# ticktock.net
KiCad netlist of a schematic drawn in EAGLE
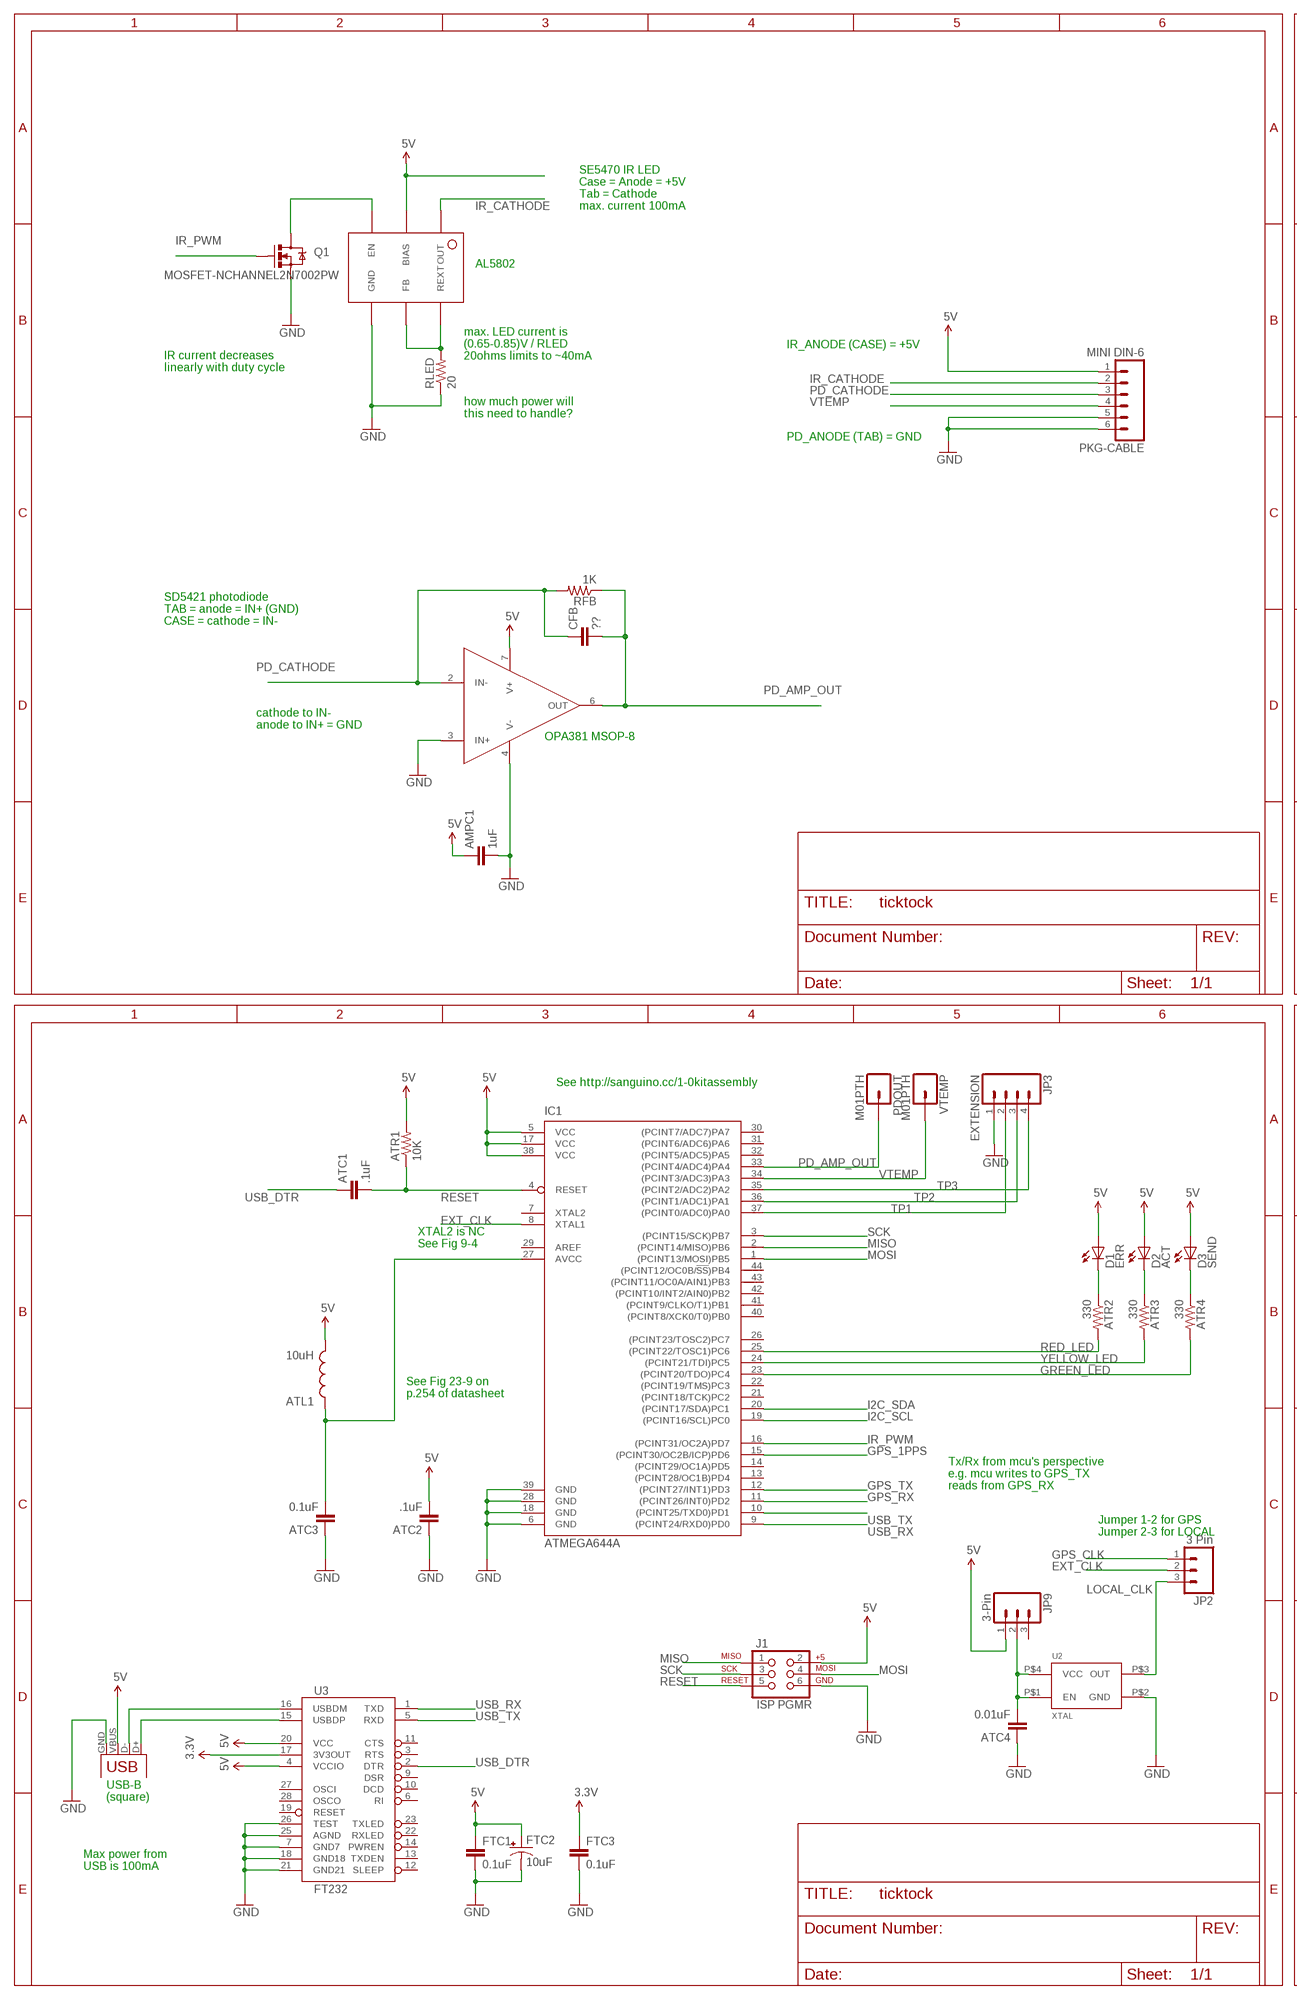
[diagram p0: schematic, sheet 1, part 1 of 2]
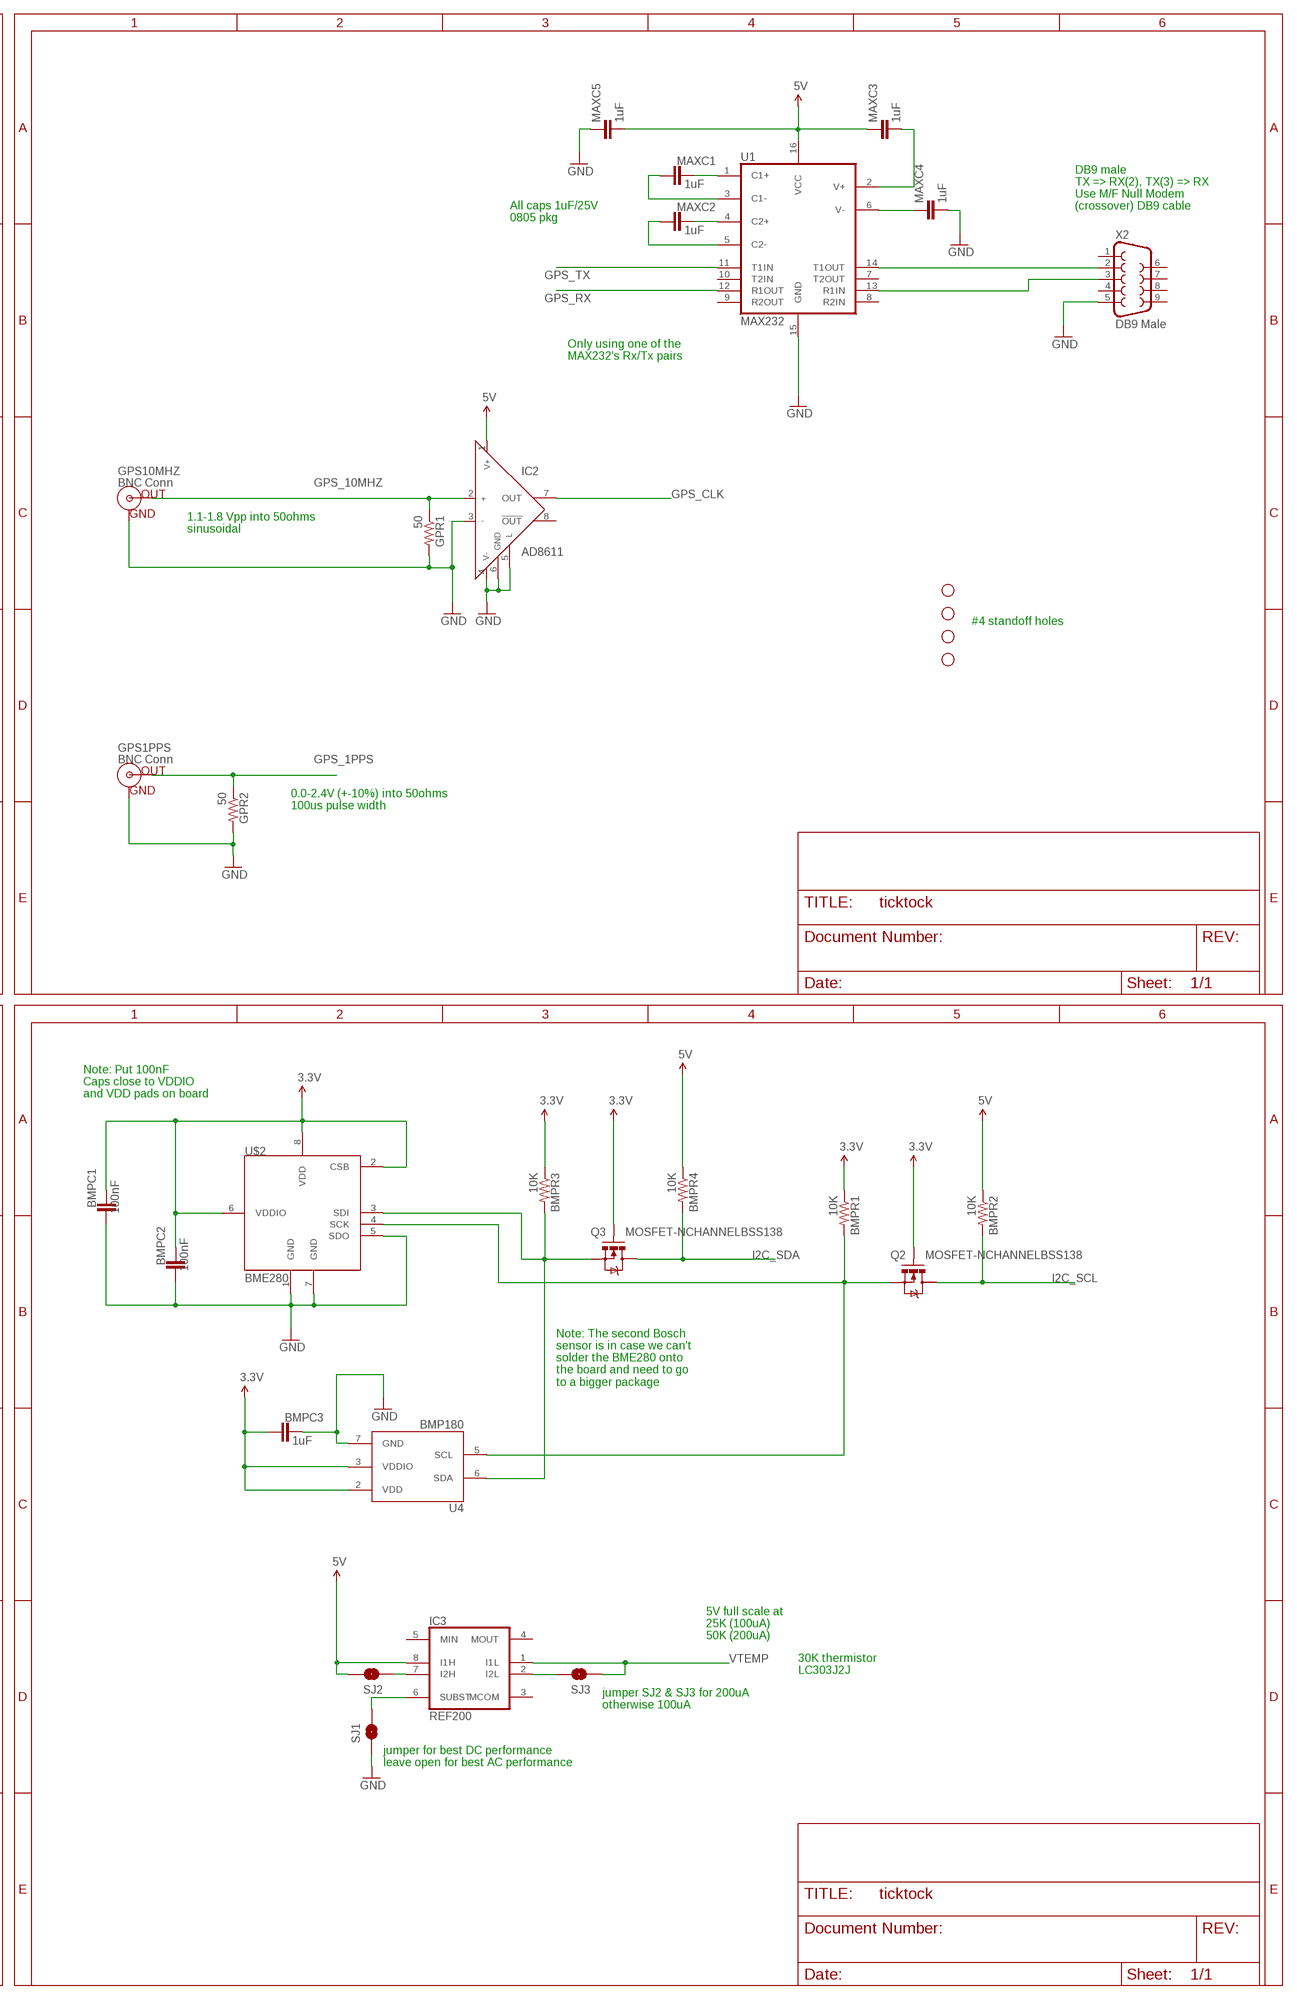
[diagram p1: schematic, sheet 1, part 2 of 2]

(export (version "E")
  (design (tool "Eeschema 10.0.6"))
  (components
    (comp (ref "AMPC1")
      (value "1uF")
      (footprint "eagle-import:0805")
      (libsource (lib "eagle-import") (part "CAP0805"))
    )
    (comp (ref "ATC1")
      (value ".1uF")
      (footprint "eagle-import:0805")
      (libsource (lib "eagle-import") (part "CAP0805"))
    )
    (comp (ref "ATC2")
      (value ".1uF")
      (footprint "eagle-import:0805")
      (libsource (lib "eagle-import") (part "CAP0805"))
    )
    (comp (ref "ATC3")
      (value "0.1uF")
      (footprint "eagle-import:0805")
      (libsource (lib "eagle-import") (part "CAP0805"))
    )
    (comp (ref "ATC4")
      (value "0.01uF")
      (footprint "eagle-import:0805")
      (libsource (lib "eagle-import") (part "CAP0805"))
    )
    (comp (ref "ATL1")
      (value "10uH")
      (footprint "eagle-import:0805")
      (libsource (lib "eagle-import") (part "INDUCTOR0805"))
    )
    (comp (ref "ATR1")
      (value "10K")
      (footprint "eagle-import:0805")
      (libsource (lib "eagle-import") (part "RESISTOR0805-RES"))
    )
    (comp (ref "ATR2")
      (value "330")
      (footprint "eagle-import:0805")
      (libsource (lib "eagle-import") (part "RESISTOR0805-RES"))
    )
    (comp (ref "ATR3")
      (value "330")
      (footprint "eagle-import:0805")
      (libsource (lib "eagle-import") (part "RESISTOR0805-RES"))
    )
    (comp (ref "ATR4")
      (value "330")
      (footprint "eagle-import:0805")
      (libsource (lib "eagle-import") (part "RESISTOR0805-RES"))
    )
    (comp (ref "BMPC1")
      (value "100nF")
      (footprint "eagle-import:0805")
      (libsource (lib "eagle-import") (part "CAP0805"))
    )
    (comp (ref "BMPC2")
      (value "100nF")
      (footprint "eagle-import:0805")
      (libsource (lib "eagle-import") (part "CAP0805"))
    )
    (comp (ref "BMPC3")
      (value "1uF")
      (footprint "eagle-import:0805")
      (libsource (lib "eagle-import") (part "CAP0805"))
    )
    (comp (ref "BMPR1")
      (value "10K")
      (footprint "eagle-import:0805")
      (libsource (lib "eagle-import") (part "RESISTOR0805-RES"))
    )
    (comp (ref "BMPR2")
      (value "10K")
      (footprint "eagle-import:0805")
      (libsource (lib "eagle-import") (part "RESISTOR0805-RES"))
    )
    (comp (ref "BMPR3")
      (value "10K")
      (footprint "eagle-import:0805")
      (libsource (lib "eagle-import") (part "RESISTOR0805-RES"))
    )
    (comp (ref "BMPR4")
      (value "10K")
      (footprint "eagle-import:0805")
      (libsource (lib "eagle-import") (part "RESISTOR0805-RES"))
    )
    (comp (ref "CFB")
      (value "??")
      (footprint "eagle-import:0805")
      (libsource (lib "eagle-import") (part "CAP0805"))
    )
    (comp (ref "D1")
      (value "ERR")
      (footprint "eagle-import:LED-1206")
      (libsource (lib "eagle-import") (part "LED-REDLILYPAD"))
    )
    (comp (ref "D2")
      (value "ACT")
      (footprint "eagle-import:LED-1206")
      (libsource (lib "eagle-import") (part "LED-YELLOWLILYPAD"))
    )
    (comp (ref "D3")
      (value "SEND")
      (footprint "eagle-import:LED-1206")
      (libsource (lib "eagle-import") (part "LED-GREENLILYPAD"))
    )
    (comp (ref "FTC1")
      (value "0.1uF")
      (footprint "eagle-import:0805")
      (libsource (lib "eagle-import") (part "CAP0805"))
    )
    (comp (ref "FTC2")
      (value "10uF")
      (footprint "eagle-import:EIA3216")
      (libsource (lib "eagle-import") (part "CAP_POL1206"))
    )
    (comp (ref "FTC3")
      (value "0.1uF")
      (footprint "eagle-import:0805")
      (libsource (lib "eagle-import") (part "CAP0805"))
    )
    (comp (ref "GPR1")
      (value "50")
      (footprint "eagle-import:0805")
      (libsource (lib "eagle-import") (part "RESISTOR0805-RES"))
    )
    (comp (ref "GPR2")
      (value "50")
      (footprint "eagle-import:0805")
      (libsource (lib "eagle-import") (part "RESISTOR0805-RES"))
    )
    (comp (ref "GPS1PPS")
      (value "BNC Conn")
      (footprint "eagle-import:BNC")
      (libsource (lib "eagle-import") (part "BNCPTH"))
    )
    (comp (ref "GPS10MHZ")
      (value "BNC Conn")
      (footprint "eagle-import:BNC")
      (libsource (lib "eagle-import") (part "BNCPTH"))
    )
    (comp (ref "IC1")
      (value "ATMEGA644A")
      (footprint "eagle-import:TQFP44")
      (fields (field (name "MPN") "ATMEGA644PV-10AU"))
      (libsource (lib "eagle-import") (part "ATMEGA644A"))
    )
    (comp (ref "IC2")
      (value "AD8611")
      (footprint "eagle-import:MSOP08")
      (fields (field (name "MPN") "AD8611ARMZ-R2"))
      (libsource (lib "eagle-import") (part "AD8611RM"))
    )
    (comp (ref "IC3")
      (value "REF200")
      (footprint "eagle-import:SO08")
      (fields (field (name "MF") "TEXAS INSTRUMENTS") (field (name "MPN") "REF200AU"))
      (libsource (lib "eagle-import") (part "REF200U"))
    )
    (comp (ref "IC4")
      (value "OPA381")
      (footprint "eagle-import:MSOP08")
      (libsource (lib "eagle-import") (part "OPA381"))
    )
    (comp (ref "IC5")
      (value "AL5802")
      (footprint "eagle-import:AL5802")
      (libsource (lib "eagle-import") (part "AL5802AL5802"))
    )
    (comp (ref "J1")
      (value "ISP PGMR")
      (footprint "eagle-import:2X3-NS")
      (libsource (lib "eagle-import") (part "AVR_SPI_PRG_6NS"))
    )
    (comp (ref "JP1")
      (value "Square USB")
      (footprint "eagle-import:USB-B-PTH")
      (libsource (lib "eagle-import") (part "USBPTH"))
    )
    (comp (ref "JP2")
      (value "3 Pin")
      (footprint "eagle-import:1X03_LOCK")
      (libsource (lib "eagle-import") (part "M03LOCK"))
    )
    (comp (ref "JP3")
      (value "EXTENSION")
      (footprint "eagle-import:1X04_LOCK")
      (libsource (lib "eagle-import") (part "M04LOCK"))
    )
    (comp (ref "JP9")
      (value "3-Pin")
      (footprint "eagle-import:1X03_LOCK")
      (libsource (lib "eagle-import") (part "M03LOCK"))
    )
    (comp (ref "MAXC1")
      (value "1uF")
      (footprint "eagle-import:0805")
      (libsource (lib "eagle-import") (part "CAP0805"))
    )
    (comp (ref "MAXC2")
      (value "1uF")
      (footprint "eagle-import:0805")
      (libsource (lib "eagle-import") (part "CAP0805"))
    )
    (comp (ref "MAXC3")
      (value "1uF")
      (footprint "eagle-import:0805")
      (libsource (lib "eagle-import") (part "CAP0805"))
    )
    (comp (ref "MAXC4")
      (value "1uF")
      (footprint "eagle-import:0805")
      (libsource (lib "eagle-import") (part "CAP0805"))
    )
    (comp (ref "MAXC5")
      (value "1uF")
      (footprint "eagle-import:0805")
      (libsource (lib "eagle-import") (part "CAP0805"))
    )
    (comp (ref "PDOUT")
      (value "M01PTH")
      (footprint "eagle-import:1X01")
      (libsource (lib "eagle-import") (part "M01PTH"))
    )
    (comp (ref "PKG-CABLE")
      (value "MINI DIN-6")
      (footprint "eagle-import:MINI-DIN6")
      (libsource (lib "eagle-import") (part "MINI-DIN6PTH"))
    )
    (comp (ref "Q1")
      (value "MOSFET-NCHANNEL2N7002PW")
      (footprint "eagle-import:SOT323")
      (libsource (lib "eagle-import") (part "MOSFET-NCHANNEL2N7002PW"))
    )
    (comp (ref "Q2")
      (value "MOSFET-NCHANNELBSS138")
      (footprint "eagle-import:SOT23")
      (libsource (lib "eagle-import") (part "MOSFET-NCHANNELBSS138"))
    )
    (comp (ref "Q3")
      (value "MOSFET-NCHANNELBSS138")
      (footprint "eagle-import:SOT23")
      (libsource (lib "eagle-import") (part "MOSFET-NCHANNELBSS138"))
    )
    (comp (ref "RFB")
      (value "1K")
      (footprint "eagle-import:0805")
      (libsource (lib "eagle-import") (part "RESISTOR0805-RES"))
    )
    (comp (ref "RLED")
      (value "20")
      (footprint "eagle-import:0805")
      (libsource (lib "eagle-import") (part "RESISTOR0805-RES"))
    )
    (comp (ref "SJ1")
      (value "SOLDERJUMPERNO")
      (footprint "eagle-import:SJ_2S-NO")
      (libsource (lib "eagle-import") (part "SOLDERJUMPERNO"))
    )
    (comp (ref "SJ2")
      (value "SOLDERJUMPERNO")
      (footprint "eagle-import:SJ_2S-NO")
      (libsource (lib "eagle-import") (part "SOLDERJUMPERNO"))
    )
    (comp (ref "SJ3")
      (value "SOLDERJUMPERNO")
      (footprint "eagle-import:SJ_2S-NO")
      (libsource (lib "eagle-import") (part "SOLDERJUMPERNO"))
    )
    (comp (ref "STANDOFF1")
      (value "STAND-OFF")
      (footprint "eagle-import:STAND-OFF")
      (libsource (lib "eagle-import") (part "STAND-OFF"))
    )
    (comp (ref "STANDOFF2")
      (value "STAND-OFF")
      (footprint "eagle-import:STAND-OFF")
      (libsource (lib "eagle-import") (part "STAND-OFF"))
    )
    (comp (ref "STANDOFF3")
      (value "STAND-OFF")
      (footprint "eagle-import:STAND-OFF")
      (libsource (lib "eagle-import") (part "STAND-OFF"))
    )
    (comp (ref "STANDOFF4")
      (value "STAND-OFF")
      (footprint "eagle-import:STAND-OFF")
      (libsource (lib "eagle-import") (part "STAND-OFF"))
    )
    (comp (ref "U$2")
      (value "BME280")
      (footprint "eagle-import:BME280")
      (libsource (lib "eagle-import") (part "BME280BME280-LGA"))
    )
    (comp (ref "U1")
      (value "MAX232")
      (footprint "eagle-import:SO016")
      (libsource (lib "eagle-import") (part "MAX232SOIC16"))
    )
    (comp (ref "U2")
      (value "XTAL")
      (footprint "eagle-import:CRYSTAL-SMD-7X5")
      (libsource (lib "eagle-import") (part "OSCILLATORSMD"))
    )
    (comp (ref "U3")
      (value "FT232")
      (footprint "eagle-import:SSOP28DB")
      (libsource (lib "eagle-import") (part "FT232RLSSOP"))
    )
    (comp (ref "U4")
      (value "BMP180")
      (footprint "eagle-import:BMP180")
      (libsource (lib "eagle-import") (part "BMP180"))
    )
    (comp (ref "VTEMP")
      (value "M01PTH")
      (footprint "eagle-import:1X01")
      (libsource (lib "eagle-import") (part "M01PTH"))
    )
    (comp (ref "X2")
      (value "DB9 Male")
      (footprint "eagle-import:DB9_MALE")
      (libsource (lib "eagle-import") (part "DB9MALE"))
    )
  )
  (nets
    (net (code "1") (name "/EXT_CLK") (class "Default")
      (node (ref "IC1") (pin "8") (pinfunction "XTAL1_8") (pintype "bidirectional"))
      (node (ref "JP2") (pin "2") (pinfunction "2_2") (pintype "passive"))
    )
    (net (code "2") (name "/GPS_1PPS") (class "Default")
      (node (ref "GPR2") (pin "1") (pinfunction "1_1") (pintype "passive"))
      (node (ref "GPS1PPS") (pin "S") (pinfunction "OUT_S") (pintype "bidirectional"))
      (node (ref "IC1") (pin "15") (pinfunction "(PCINT30/OC2B/ICP)PD6_15") (pintype "bidirectional"))
    )
    (net (code "3") (name "/GPS_10MHZ") (class "Default")
      (node (ref "GPR1") (pin "1") (pinfunction "1_1") (pintype "passive"))
      (node (ref "GPS10MHZ") (pin "S") (pinfunction "OUT_S") (pintype "bidirectional"))
      (node (ref "IC2") (pin "2") (pinfunction "IN+_2") (pintype "input"))
    )
    (net (code "4") (name "/GPS_CLK") (class "Default")
      (node (ref "IC2") (pin "7") (pinfunction "OUT_7") (pintype "output"))
      (node (ref "JP2") (pin "1") (pinfunction "1_1") (pintype "passive"))
    )
    (net (code "5") (name "/GPS_RX") (class "Default")
      (node (ref "IC1") (pin "11") (pinfunction "(PCINT26/INT0)PD2_11") (pintype "bidirectional"))
      (node (ref "U1") (pin "12") (pinfunction "R1OUT_12") (pintype "output"))
    )
    (net (code "6") (name "/GPS_TX") (class "Default")
      (node (ref "IC1") (pin "12") (pinfunction "(PCINT27/INT1)PD3_12") (pintype "bidirectional"))
      (node (ref "U1") (pin "11") (pinfunction "T1IN_11") (pintype "input"))
    )
    (net (code "7") (name "/GREEN_LED") (class "Default")
      (node (ref "ATR4") (pin "2") (pinfunction "2_2") (pintype "passive"))
      (node (ref "IC1") (pin "23") (pinfunction "(PCINT20/TDO)PC4_23") (pintype "output"))
    )
    (net (code "8") (name "/I2C_SCL") (class "Default")
      (node (ref "BMPR2") (pin "2") (pinfunction "2_2") (pintype "passive"))
      (node (ref "IC1") (pin "19") (pinfunction "(PCINT16/SCL)PC0_19") (pintype "output"))
      (node (ref "Q2") (pin "3") (pinfunction "D_3") (pintype "passive"))
    )
    (net (code "9") (name "/I2C_SDA") (class "Default")
      (node (ref "BMPR4") (pin "2") (pinfunction "2_2") (pintype "passive"))
      (node (ref "IC1") (pin "20") (pinfunction "(PCINT17/SDA)PC1_20") (pintype "output"))
      (node (ref "Q3") (pin "3") (pinfunction "D_3") (pintype "passive"))
    )
    (net (code "10") (name "/IR_CATHODE") (class "Default")
      (node (ref "IC5") (pin "OUT") (pinfunction "OUT_OUT") (pintype "bidirectional"))
      (node (ref "PKG-CABLE") (pin "2") (pinfunction "2_2") (pintype "passive"))
    )
    (net (code "11") (name "/IR_PWM") (class "Default")
      (node (ref "IC1") (pin "16") (pinfunction "(PCINT31/OC2A)PD7_16") (pintype "bidirectional"))
      (node (ref "Q1") (pin "1") (pinfunction "G_1") (pintype "passive"))
    )
    (net (code "12") (name "/LOCAL_CLK") (class "Default")
      (node (ref "JP2") (pin "3") (pinfunction "3_3") (pintype "passive"))
      (node (ref "U2") (pin "P$3") (pinfunction "OUT_P$3") (pintype "bidirectional"))
    )
    (net (code "13") (name "/MISO") (class "Default")
      (node (ref "IC1") (pin "2") (pinfunction "(PCINT14/MISO)PB6_2") (pintype "bidirectional"))
      (node (ref "J1") (pin "1") (pinfunction "1_1") (pintype "passive"))
    )
    (net (code "14") (name "/MOSI") (class "Default")
      (node (ref "IC1") (pin "1") (pinfunction "(PCINT13/MOSI)PB5_1") (pintype "bidirectional"))
      (node (ref "J1") (pin "4") (pinfunction "4_4") (pintype "passive"))
    )
    (net (code "15") (name "/PD_AMP_OUT") (class "Default")
      (node (ref "CFB") (pin "2") (pinfunction "2_2") (pintype "passive"))
      (node (ref "IC1") (pin "33") (pinfunction "(PCINT4/ADC4)PA4_33") (pintype "bidirectional"))
      (node (ref "IC4") (pin "6") (pinfunction "OUT_6") (pintype "bidirectional"))
      (node (ref "PDOUT") (pin "1") (pinfunction "1_1") (pintype "passive"))
      (node (ref "RFB") (pin "1") (pinfunction "1_1") (pintype "passive"))
    )
    (net (code "16") (name "/PD_CATHODE") (class "Default")
      (node (ref "CFB") (pin "1") (pinfunction "1_1") (pintype "passive"))
      (node (ref "IC4") (pin "2") (pinfunction "IN-_2") (pintype "bidirectional"))
      (node (ref "PKG-CABLE") (pin "3") (pinfunction "3_3") (pintype "passive"))
      (node (ref "RFB") (pin "2") (pinfunction "2_2") (pintype "passive"))
    )
    (net (code "17") (name "/RED_LED") (class "Default")
      (node (ref "ATR2") (pin "2") (pinfunction "2_2") (pintype "passive"))
      (node (ref "IC1") (pin "25") (pinfunction "(PCINT22/TOSC1)PC6_25") (pintype "output"))
    )
    (net (code "18") (name "/RESET") (class "Default")
      (node (ref "ATC1") (pin "2") (pinfunction "2_2") (pintype "passive"))
      (node (ref "ATR1") (pin "1") (pinfunction "1_1") (pintype "passive"))
      (node (ref "IC1") (pin "4") (pinfunction "RESET_4") (pintype "input"))
      (node (ref "J1") (pin "5") (pinfunction "5_5") (pintype "passive"))
    )
    (net (code "19") (name "/SCK") (class "Default")
      (node (ref "IC1") (pin "3") (pinfunction "(PCINT15/SCK)PB7_3") (pintype "bidirectional"))
      (node (ref "J1") (pin "3") (pinfunction "3_3") (pintype "passive"))
    )
    (net (code "20") (name "/TP1") (class "Default")
      (node (ref "IC1") (pin "37") (pinfunction "(PCINT0/ADC0)PA0_37") (pintype "bidirectional"))
      (node (ref "JP3") (pin "2") (pinfunction "2_2") (pintype "passive"))
    )
    (net (code "21") (name "/TP2") (class "Default")
      (node (ref "IC1") (pin "36") (pinfunction "(PCINT1/ADC1)PA1_36") (pintype "bidirectional"))
      (node (ref "JP3") (pin "3") (pinfunction "3_3") (pintype "passive"))
    )
    (net (code "22") (name "/TP3") (class "Default")
      (node (ref "IC1") (pin "35") (pinfunction "(PCINT2/ADC2)PA2_35") (pintype "bidirectional"))
      (node (ref "JP3") (pin "4") (pinfunction "4_4") (pintype "passive"))
    )
    (net (code "23") (name "/USB_DTR") (class "Default")
      (node (ref "ATC1") (pin "1") (pinfunction "1_1") (pintype "passive"))
      (node (ref "U3") (pin "2") (pinfunction "DTR_2") (pintype "output"))
    )
    (net (code "24") (name "/USB_RX") (class "Default")
      (node (ref "IC1") (pin "9") (pinfunction "(PCINT24/RXD0)PD0_9") (pintype "bidirectional"))
      (node (ref "U3") (pin "1") (pinfunction "TXD_1") (pintype "output"))
    )
    (net (code "25") (name "/USB_TX") (class "Default")
      (node (ref "IC1") (pin "10") (pinfunction "(PCINT25/TXD0)PD1_10") (pintype "bidirectional"))
      (node (ref "U3") (pin "5") (pinfunction "RXD_5") (pintype "input"))
    )
    (net (code "26") (name "/VTEMP") (class "Default")
      (node (ref "IC1") (pin "34") (pinfunction "(PCINT3/ADC3)PA3_34") (pintype "bidirectional"))
      (node (ref "IC3") (pin "1") (pinfunction "I1L_1") (pintype "passive"))
      (node (ref "PKG-CABLE") (pin "4") (pinfunction "4_4") (pintype "passive"))
      (node (ref "SJ3") (pin "1") (pinfunction "1_1") (pintype "passive"))
      (node (ref "VTEMP") (pin "1") (pinfunction "1_1") (pintype "passive"))
    )
    (net (code "27") (name "/YELLOW_LED") (class "Default")
      (node (ref "ATR3") (pin "2") (pinfunction "2_2") (pintype "passive"))
      (node (ref "IC1") (pin "24") (pinfunction "(PCINT21/TDI)PC5_24") (pintype "output"))
    )
    (net (code "28") (name "3.3V") (class "Default")
      (node (ref "BMPC1") (pin "2") (pinfunction "2_2") (pintype "passive"))
      (node (ref "BMPC2") (pin "2") (pinfunction "2_2") (pintype "passive"))
      (node (ref "BMPC3") (pin "1") (pinfunction "1_1") (pintype "passive"))
      (node (ref "BMPR1") (pin "1") (pinfunction "1_1") (pintype "passive"))
      (node (ref "BMPR3") (pin "1") (pinfunction "1_1") (pintype "passive"))
      (node (ref "FTC3") (pin "1") (pinfunction "1_1") (pintype "passive"))
      (node (ref "Q2") (pin "1") (pinfunction "G_1") (pintype "passive"))
      (node (ref "Q3") (pin "1") (pinfunction "G_1") (pintype "passive"))
      (node (ref "U$2") (pin "2") (pinfunction "CSB_2") (pintype "bidirectional"))
      (node (ref "U$2") (pin "6") (pinfunction "VDDIO_6") (pintype "bidirectional"))
      (node (ref "U$2") (pin "8") (pinfunction "VDD_8") (pintype "bidirectional"))
      (node (ref "U3") (pin "17") (pinfunction "3V3OUT_17") (pintype "output"))
      (node (ref "U4") (pin "2") (pinfunction "VDD_2") (pintype "power_in"))
      (node (ref "U4") (pin "3") (pinfunction "VDDIO_3") (pintype "power_in"))
    )
    (net (code "29") (name "5V") (class "Default")
      (node (ref "AMPC1") (pin "1") (pinfunction "1_1") (pintype "passive"))
      (node (ref "ATC2") (pin "2") (pinfunction "2_2") (pintype "passive"))
      (node (ref "ATL1") (pin "2") (pinfunction "2_2") (pintype "passive"))
      (node (ref "ATR1") (pin "2") (pinfunction "2_2") (pintype "passive"))
      (node (ref "BMPR2") (pin "1") (pinfunction "1_1") (pintype "passive"))
      (node (ref "BMPR4") (pin "1") (pinfunction "1_1") (pintype "passive"))
      (node (ref "D1") (pin "A") (pinfunction "A_A") (pintype "passive"))
      (node (ref "D2") (pin "A") (pinfunction "A_A") (pintype "passive"))
      (node (ref "D3") (pin "A") (pinfunction "A_A") (pintype "passive"))
      (node (ref "FTC1") (pin "1") (pinfunction "1_1") (pintype "passive"))
      (node (ref "FTC2") (pin "A") (pinfunction "+_A") (pintype "passive"))
      (node (ref "IC1") (pin "17") (pinfunction "VCC_17") (pintype "power_in"))
      (node (ref "IC1") (pin "38") (pinfunction "VCC_38") (pintype "power_in"))
      (node (ref "IC1") (pin "5") (pinfunction "VCC_5") (pintype "power_in"))
      (node (ref "IC2") (pin "1") (pinfunction "V+_1") (pintype "power_in"))
      (node (ref "IC3") (pin "8") (pinfunction "I1H_8") (pintype "passive"))
      (node (ref "IC4") (pin "7") (pinfunction "V+_7") (pintype "bidirectional"))
      (node (ref "IC5") (pin "BIAS") (pinfunction "BIAS_BIAS") (pintype "bidirectional"))
      (node (ref "J1") (pin "2") (pinfunction "2_2") (pintype "passive"))
      (node (ref "JP1") (pin "VBUS") (pinfunction "VBUS_VBUS") (pintype "bidirectional"))
      (node (ref "JP9") (pin "1") (pinfunction "1_1") (pintype "passive"))
      (node (ref "MAXC3") (pin "1") (pinfunction "1_1") (pintype "passive"))
      (node (ref "MAXC5") (pin "2") (pinfunction "2_2") (pintype "passive"))
      (node (ref "PKG-CABLE") (pin "1") (pinfunction "1_1") (pintype "passive"))
      (node (ref "SJ2") (pin "2") (pinfunction "2_2") (pintype "passive"))
      (node (ref "U1") (pin "16") (pinfunction "VCC_16") (pintype "bidirectional"))
      (node (ref "U3") (pin "20") (pinfunction "VCC_20") (pintype "power_in"))
      (node (ref "U3") (pin "4") (pinfunction "VCCIO_4") (pintype "power_in"))
    )
    (net (code "30") (name "GND") (class "Default")
      (node (ref "AMPC1") (pin "2") (pinfunction "2_2") (pintype "passive"))
      (node (ref "ATC2") (pin "1") (pinfunction "1_1") (pintype "passive"))
      (node (ref "ATC3") (pin "1") (pinfunction "1_1") (pintype "passive"))
      (node (ref "ATC4") (pin "1") (pinfunction "1_1") (pintype "passive"))
      (node (ref "BMPC1") (pin "1") (pinfunction "1_1") (pintype "passive"))
      (node (ref "BMPC2") (pin "1") (pinfunction "1_1") (pintype "passive"))
      (node (ref "BMPC3") (pin "2") (pinfunction "2_2") (pintype "passive"))
      (node (ref "FTC1") (pin "2") (pinfunction "2_2") (pintype "passive"))
      (node (ref "FTC2") (pin "C") (pinfunction "-_C") (pintype "passive"))
      (node (ref "FTC3") (pin "2") (pinfunction "2_2") (pintype "passive"))
      (node (ref "GPR1") (pin "2") (pinfunction "2_2") (pintype "passive"))
      (node (ref "GPR2") (pin "2") (pinfunction "2_2") (pintype "passive"))
      (node (ref "GPS10MHZ") (pin "GND") (pinfunction "GND_GND") (pintype "bidirectional"))
      (node (ref "GPS1PPS") (pin "GND") (pinfunction "GND_GND") (pintype "bidirectional"))
      (node (ref "IC1") (pin "18") (pinfunction "GND_18") (pintype "power_in"))
      (node (ref "IC1") (pin "28") (pinfunction "GND_28") (pintype "power_in"))
      (node (ref "IC1") (pin "39") (pinfunction "GND_39") (pintype "power_in"))
      (node (ref "IC1") (pin "6") (pinfunction "GND_6") (pintype "power_in"))
      (node (ref "IC2") (pin "3") (pinfunction "IN-_3") (pintype "input"))
      (node (ref "IC2") (pin "4") (pinfunction "V-_4") (pintype "power_in"))
      (node (ref "IC2") (pin "5") (pinfunction "L_5") (pintype "input"))
      (node (ref "IC2") (pin "6") (pinfunction "GND_6") (pintype "power_in"))
      (node (ref "IC4") (pin "3") (pinfunction "IN+_3") (pintype "bidirectional"))
      (node (ref "IC4") (pin "4") (pinfunction "V-_4") (pintype "bidirectional"))
      (node (ref "IC5") (pin "GND") (pinfunction "GND_GND") (pintype "bidirectional"))
      (node (ref "J1") (pin "6") (pinfunction "6_6") (pintype "passive"))
      (node (ref "JP1") (pin "GND") (pinfunction "GND_GND") (pintype "bidirectional"))
      (node (ref "JP3") (pin "1") (pinfunction "1_1") (pintype "passive"))
      (node (ref "MAXC4") (pin "2") (pinfunction "2_2") (pintype "passive"))
      (node (ref "MAXC5") (pin "1") (pinfunction "1_1") (pintype "passive"))
      (node (ref "PKG-CABLE") (pin "5") (pinfunction "5_5") (pintype "passive"))
      (node (ref "PKG-CABLE") (pin "6") (pinfunction "6_6") (pintype "passive"))
      (node (ref "Q1") (pin "2") (pinfunction "S_2") (pintype "passive"))
      (node (ref "RLED") (pin "1") (pinfunction "1_1") (pintype "passive"))
      (node (ref "SJ1") (pin "1") (pinfunction "1_1") (pintype "passive"))
      (node (ref "U$2") (pin "1") (pinfunction "GND_1") (pintype "bidirectional"))
      (node (ref "U$2") (pin "5") (pinfunction "SDO_5") (pintype "bidirectional"))
      (node (ref "U$2") (pin "7") (pinfunction "GND_7") (pintype "bidirectional"))
      (node (ref "U1") (pin "15") (pinfunction "GND_15") (pintype "bidirectional"))
      (node (ref "U2") (pin "P$2") (pinfunction "GND_P$2") (pintype "bidirectional"))
      (node (ref "U3") (pin "18") (pinfunction "GND18_18") (pintype "power_in"))
      (node (ref "U3") (pin "21") (pinfunction "GND21_21") (pintype "power_in"))
      (node (ref "U3") (pin "25") (pinfunction "AGND_25") (pintype "power_in"))
      (node (ref "U3") (pin "26") (pinfunction "TEST_26") (pintype "input"))
      (node (ref "U3") (pin "7") (pinfunction "GND7_7") (pintype "power_in"))
      (node (ref "U4") (pin "7") (pinfunction "GND_7") (pintype "power_in"))
      (node (ref "X2") (pin "5") (pinfunction "5_5") (pintype "passive"))
    )
    (net (code "31") (name "Net-(ATR2-Pad1)") (class "Default")
      (node (ref "ATR2") (pin "1") (pinfunction "1_1") (pintype "passive"))
      (node (ref "D1") (pin "C") (pinfunction "C_C") (pintype "passive"))
    )
    (net (code "32") (name "Net-(ATR3-Pad1)") (class "Default")
      (node (ref "ATR3") (pin "1") (pinfunction "1_1") (pintype "passive"))
      (node (ref "D2") (pin "C") (pinfunction "C_C") (pintype "passive"))
    )
    (net (code "33") (name "Net-(ATR4-Pad1)") (class "Default")
      (node (ref "ATR4") (pin "1") (pinfunction "1_1") (pintype "passive"))
      (node (ref "D3") (pin "C") (pinfunction "C_C") (pintype "passive"))
    )
    (net (code "34") (name "Net-(IC1-AVCC)") (class "Default")
      (node (ref "ATC3") (pin "2") (pinfunction "2_2") (pintype "passive"))
      (node (ref "ATL1") (pin "1") (pinfunction "1_1") (pintype "passive"))
      (node (ref "IC1") (pin "27") (pinfunction "AVCC_27") (pintype "power_in"))
    )
    (net (code "35") (name "Net-(IC3-I2H)") (class "Default")
      (node (ref "IC3") (pin "7") (pinfunction "I2H_7") (pintype "passive"))
      (node (ref "SJ2") (pin "1") (pinfunction "1_1") (pintype "passive"))
    )
    (net (code "36") (name "Net-(IC3-I2L)") (class "Default")
      (node (ref "IC3") (pin "2") (pinfunction "I2L_2") (pintype "passive"))
      (node (ref "SJ3") (pin "2") (pinfunction "2_2") (pintype "passive"))
    )
    (net (code "37") (name "Net-(IC3-SUBST)") (class "Default")
      (node (ref "IC3") (pin "6") (pinfunction "SUBST_6") (pintype "passive"))
      (node (ref "SJ1") (pin "2") (pinfunction "2_2") (pintype "passive"))
    )
    (net (code "38") (name "Net-(IC5-PadFB)") (class "Default")
      (node (ref "IC5") (pin "FB") (pinfunction "FB_FB") (pintype "bidirectional"))
      (node (ref "IC5") (pin "REXT") (pinfunction "REXT_REXT") (pintype "bidirectional"))
      (node (ref "RLED") (pin "2") (pinfunction "2_2") (pintype "passive"))
    )
    (net (code "39") (name "Net-(Q1-D)") (class "Default")
      (node (ref "IC5") (pin "EN") (pinfunction "EN_EN") (pintype "bidirectional"))
      (node (ref "Q1") (pin "3") (pinfunction "D_3") (pintype "passive"))
    )
    (net (code "40") (name "Net-(Q2-S)") (class "Default")
      (node (ref "BMPR1") (pin "2") (pinfunction "2_2") (pintype "passive"))
      (node (ref "Q2") (pin "2") (pinfunction "S_2") (pintype "passive"))
      (node (ref "U$2") (pin "4") (pinfunction "SCK_4") (pintype "bidirectional"))
      (node (ref "U4") (pin "5") (pinfunction "SCL_5") (pintype "input"))
    )
    (net (code "41") (name "Net-(Q3-S)") (class "Default")
      (node (ref "BMPR3") (pin "2") (pinfunction "2_2") (pintype "passive"))
      (node (ref "Q3") (pin "2") (pinfunction "S_2") (pintype "passive"))
      (node (ref "U$2") (pin "3") (pinfunction "SDI_3") (pintype "bidirectional"))
      (node (ref "U4") (pin "6") (pinfunction "SDA_6") (pintype "bidirectional"))
    )
    (net (code "42") (name "Net-(U1-C1+)") (class "Default")
      (node (ref "MAXC1") (pin "2") (pinfunction "2_2") (pintype "passive"))
      (node (ref "U1") (pin "1") (pinfunction "C1+_1") (pintype "bidirectional"))
    )
    (net (code "43") (name "Net-(U1-C1-)") (class "Default")
      (node (ref "MAXC1") (pin "1") (pinfunction "1_1") (pintype "passive"))
      (node (ref "U1") (pin "3") (pinfunction "C1-_3") (pintype "bidirectional"))
    )
    (net (code "44") (name "Net-(U1-C2+)") (class "Default")
      (node (ref "MAXC2") (pin "2") (pinfunction "2_2") (pintype "passive"))
      (node (ref "U1") (pin "4") (pinfunction "C2+_4") (pintype "bidirectional"))
    )
    (net (code "45") (name "Net-(U1-C2-)") (class "Default")
      (node (ref "MAXC2") (pin "1") (pinfunction "1_1") (pintype "passive"))
      (node (ref "U1") (pin "5") (pinfunction "C2-_5") (pintype "bidirectional"))
    )
    (net (code "46") (name "Net-(U1-R1IN)") (class "Default")
      (node (ref "U1") (pin "13") (pinfunction "R1IN_13") (pintype "input"))
      (node (ref "X2") (pin "3") (pinfunction "3_3") (pintype "passive"))
    )
    (net (code "47") (name "Net-(U1-T1OUT)") (class "Default")
      (node (ref "U1") (pin "14") (pinfunction "T1OUT_14") (pintype "output"))
      (node (ref "X2") (pin "2") (pinfunction "2_2") (pintype "passive"))
    )
    (net (code "48") (name "Net-(U1-V+)") (class "Default")
      (node (ref "MAXC3") (pin "2") (pinfunction "2_2") (pintype "passive"))
      (node (ref "U1") (pin "2") (pinfunction "V+_2") (pintype "bidirectional"))
    )
    (net (code "49") (name "Net-(U1-V-)") (class "Default")
      (node (ref "MAXC4") (pin "1") (pinfunction "1_1") (pintype "passive"))
      (node (ref "U1") (pin "6") (pinfunction "V-_6") (pintype "bidirectional"))
    )
    (net (code "50") (name "Net-(U2-EN)") (class "Default")
      (node (ref "ATC4") (pin "2") (pinfunction "2_2") (pintype "passive"))
      (node (ref "JP9") (pin "2") (pinfunction "2_2") (pintype "passive"))
      (node (ref "U2") (pin "P$1") (pinfunction "EN_P$1") (pintype "bidirectional"))
      (node (ref "U2") (pin "P$4") (pinfunction "VCC_P$4") (pintype "bidirectional"))
    )
    (net (code "51") (name "Net-(U3-USBDM)") (class "Default")
      (node (ref "JP1") (pin "D-") (pinfunction "D-_D-") (pintype "bidirectional"))
      (node (ref "U3") (pin "16") (pinfunction "USBDM_16") (pintype "bidirectional"))
    )
    (net (code "52") (name "Net-(U3-USBDP)") (class "Default")
      (node (ref "JP1") (pin "D+") (pinfunction "D+_D+") (pintype "bidirectional"))
      (node (ref "U3") (pin "15") (pinfunction "USBDP_15") (pintype "bidirectional"))
    )
    (net (code "53") (name "unconnected-(IC1-(PCINT5{slash}ADC5)PA5-Pad32)") (class "Default")
      (node (ref "IC1") (pin "32") (pinfunction "(PCINT5/ADC5)PA5_32") (pintype "bidirectional"))
    )
    (net (code "54") (name "unconnected-(IC1-(PCINT6{slash}ADC6)PA6-Pad31)") (class "Default")
      (node (ref "IC1") (pin "31") (pinfunction "(PCINT6/ADC6)PA6_31") (pintype "bidirectional"))
    )
    (net (code "55") (name "unconnected-(IC1-(PCINT7{slash}ADC7)PA7-Pad30)") (class "Default")
      (node (ref "IC1") (pin "30") (pinfunction "(PCINT7/ADC7)PA7_30") (pintype "bidirectional"))
    )
    (net (code "56") (name "unconnected-(IC1-(PCINT8{slash}XCK0{slash}T0)PB0-Pad40)") (class "Default")
      (node (ref "IC1") (pin "40") (pinfunction "(PCINT8/XCK0/T0)PB0_40") (pintype "bidirectional"))
    )
    (net (code "57") (name "unconnected-(IC1-(PCINT9{slash}CLKO{slash}T1)PB1-Pad41)") (class "Default")
      (node (ref "IC1") (pin "41") (pinfunction "(PCINT9/CLKO/T1)PB1_41") (pintype "bidirectional"))
    )
    (net (code "58") (name "unconnected-(IC1-(PCINT10{slash}INT2{slash}AIN0)PB2-Pad42)") (class "Default")
      (node (ref "IC1") (pin "42") (pinfunction "(PCINT10/INT2/AIN0)PB2_42") (pintype "bidirectional"))
    )
    (net (code "59") (name "unconnected-(IC1-(PCINT11{slash}OC0A{slash}AIN1)PB3-Pad43)") (class "Default")
      (node (ref "IC1") (pin "43") (pinfunction "(PCINT11/OC0A/AIN1)PB3_43") (pintype "bidirectional"))
    )
    (net (code "60") (name "unconnected-(IC1-(PCINT12{slash}OC0B{slash}~{SS})PB4-Pad44)") (class "Default")
      (node (ref "IC1") (pin "44") (pinfunction "(PCINT12/OC0B/~{SS})PB4_44") (pintype "bidirectional"))
    )
    (net (code "61") (name "unconnected-(IC1-(PCINT18{slash}TCK)PC2-Pad21)") (class "Default")
      (node (ref "IC1") (pin "21") (pinfunction "(PCINT18/TCK)PC2_21") (pintype "output"))
    )
    (net (code "62") (name "unconnected-(IC1-(PCINT19{slash}TMS)PC3-Pad22)") (class "Default")
      (node (ref "IC1") (pin "22") (pinfunction "(PCINT19/TMS)PC3_22") (pintype "output"))
    )
    (net (code "63") (name "unconnected-(IC1-(PCINT23{slash}TOSC2)PC7-Pad26)") (class "Default")
      (node (ref "IC1") (pin "26") (pinfunction "(PCINT23/TOSC2)PC7_26") (pintype "output"))
    )
    (net (code "64") (name "unconnected-(IC1-(PCINT28{slash}OC1B)PD4-Pad13)") (class "Default")
      (node (ref "IC1") (pin "13") (pinfunction "(PCINT28/OC1B)PD4_13") (pintype "bidirectional"))
    )
    (net (code "65") (name "unconnected-(IC1-(PCINT29{slash}OC1A)PD5-Pad14)") (class "Default")
      (node (ref "IC1") (pin "14") (pinfunction "(PCINT29/OC1A)PD5_14") (pintype "bidirectional"))
    )
    (net (code "66") (name "unconnected-(IC1-AREF-Pad29)") (class "Default")
      (node (ref "IC1") (pin "29") (pinfunction "AREF_29") (pintype "passive"))
    )
    (net (code "67") (name "unconnected-(IC1-XTAL2-Pad7)") (class "Default")
      (node (ref "IC1") (pin "7") (pinfunction "XTAL2_7") (pintype "bidirectional"))
    )
    (net (code "68") (name "unconnected-(IC2-~{OUT}-Pad8)") (class "Default")
      (node (ref "IC2") (pin "8") (pinfunction "~{OUT}_8") (pintype "output"))
    )
    (net (code "69") (name "unconnected-(IC3-MCOM-Pad3)") (class "Default")
      (node (ref "IC3") (pin "3") (pinfunction "MCOM_3") (pintype "passive"))
    )
    (net (code "70") (name "unconnected-(IC3-MIN-Pad5)") (class "Default")
      (node (ref "IC3") (pin "5") (pinfunction "MIN_5") (pintype "input"))
    )
    (net (code "71") (name "unconnected-(IC3-MOUT-Pad4)") (class "Default")
      (node (ref "IC3") (pin "4") (pinfunction "MOUT_4") (pintype "output"))
    )
    (net (code "72") (name "unconnected-(JP9-Pad3)") (class "Default")
      (node (ref "JP9") (pin "3") (pinfunction "3_3") (pintype "passive"))
    )
    (net (code "73") (name "unconnected-(U1-R2IN-Pad8)") (class "Default")
      (node (ref "U1") (pin "8") (pinfunction "R2IN_8") (pintype "input"))
    )
    (net (code "74") (name "unconnected-(U1-R2OUT-Pad9)") (class "Default")
      (node (ref "U1") (pin "9") (pinfunction "R2OUT_9") (pintype "output"))
    )
    (net (code "75") (name "unconnected-(U1-T2IN-Pad10)") (class "Default")
      (node (ref "U1") (pin "10") (pinfunction "T2IN_10") (pintype "input"))
    )
    (net (code "76") (name "unconnected-(U1-T2OUT-Pad7)") (class "Default")
      (node (ref "U1") (pin "7") (pinfunction "T2OUT_7") (pintype "output"))
    )
    (net (code "77") (name "unconnected-(U3-CTS-Pad11)") (class "Default")
      (node (ref "U3") (pin "11") (pinfunction "CTS_11") (pintype "input"))
    )
    (net (code "78") (name "unconnected-(U3-DCD-Pad10)") (class "Default")
      (node (ref "U3") (pin "10") (pinfunction "DCD_10") (pintype "input"))
    )
    (net (code "79") (name "unconnected-(U3-DSR-Pad9)") (class "Default")
      (node (ref "U3") (pin "9") (pinfunction "DSR_9") (pintype "input"))
    )
    (net (code "80") (name "unconnected-(U3-OSCI-Pad27)") (class "Default")
      (node (ref "U3") (pin "27") (pinfunction "OSCI_27") (pintype "input"))
    )
    (net (code "81") (name "unconnected-(U3-OSCO-Pad28)") (class "Default")
      (node (ref "U3") (pin "28") (pinfunction "OSCO_28") (pintype "output"))
    )
    (net (code "82") (name "unconnected-(U3-PWREN-Pad14)") (class "Default")
      (node (ref "U3") (pin "14") (pinfunction "PWREN_14") (pintype "input"))
    )
    (net (code "83") (name "unconnected-(U3-RESET-Pad19)") (class "Default")
      (node (ref "U3") (pin "19") (pinfunction "RESET_19") (pintype "input"))
    )
    (net (code "84") (name "unconnected-(U3-RI-Pad6)") (class "Default")
      (node (ref "U3") (pin "6") (pinfunction "RI_6") (pintype "input"))
    )
    (net (code "85") (name "unconnected-(U3-RTS-Pad3)") (class "Default")
      (node (ref "U3") (pin "3") (pinfunction "RTS_3") (pintype "output"))
    )
    (net (code "86") (name "unconnected-(U3-RXLED-Pad22)") (class "Default")
      (node (ref "U3") (pin "22") (pinfunction "RXLED_22") (pintype "input"))
    )
    (net (code "87") (name "unconnected-(U3-SLEEP-Pad12)") (class "Default")
      (node (ref "U3") (pin "12") (pinfunction "SLEEP_12") (pintype "input"))
    )
    (net (code "88") (name "unconnected-(U3-TXDEN-Pad13)") (class "Default")
      (node (ref "U3") (pin "13") (pinfunction "TXDEN_13") (pintype "input"))
    )
    (net (code "89") (name "unconnected-(U3-TXLED-Pad23)") (class "Default")
      (node (ref "U3") (pin "23") (pinfunction "TXLED_23") (pintype "input"))
    )
    (net (code "90") (name "unconnected-(X2-Pad1)") (class "Default")
      (node (ref "X2") (pin "1") (pinfunction "1_1") (pintype "passive"))
    )
    (net (code "91") (name "unconnected-(X2-Pad4)") (class "Default")
      (node (ref "X2") (pin "4") (pinfunction "4_4") (pintype "passive"))
    )
    (net (code "92") (name "unconnected-(X2-Pad6)") (class "Default")
      (node (ref "X2") (pin "6") (pinfunction "6_6") (pintype "passive"))
    )
    (net (code "93") (name "unconnected-(X2-Pad7)") (class "Default")
      (node (ref "X2") (pin "7") (pinfunction "7_7") (pintype "passive"))
    )
    (net (code "94") (name "unconnected-(X2-Pad8)") (class "Default")
      (node (ref "X2") (pin "8") (pinfunction "8_8") (pintype "passive"))
    )
    (net (code "95") (name "unconnected-(X2-Pad9)") (class "Default")
      (node (ref "X2") (pin "9") (pinfunction "9_9") (pintype "passive"))
    )
  )
)
